# GroundStationvpatryk.net
KiCad netlist of a schematic drawn in EAGLE
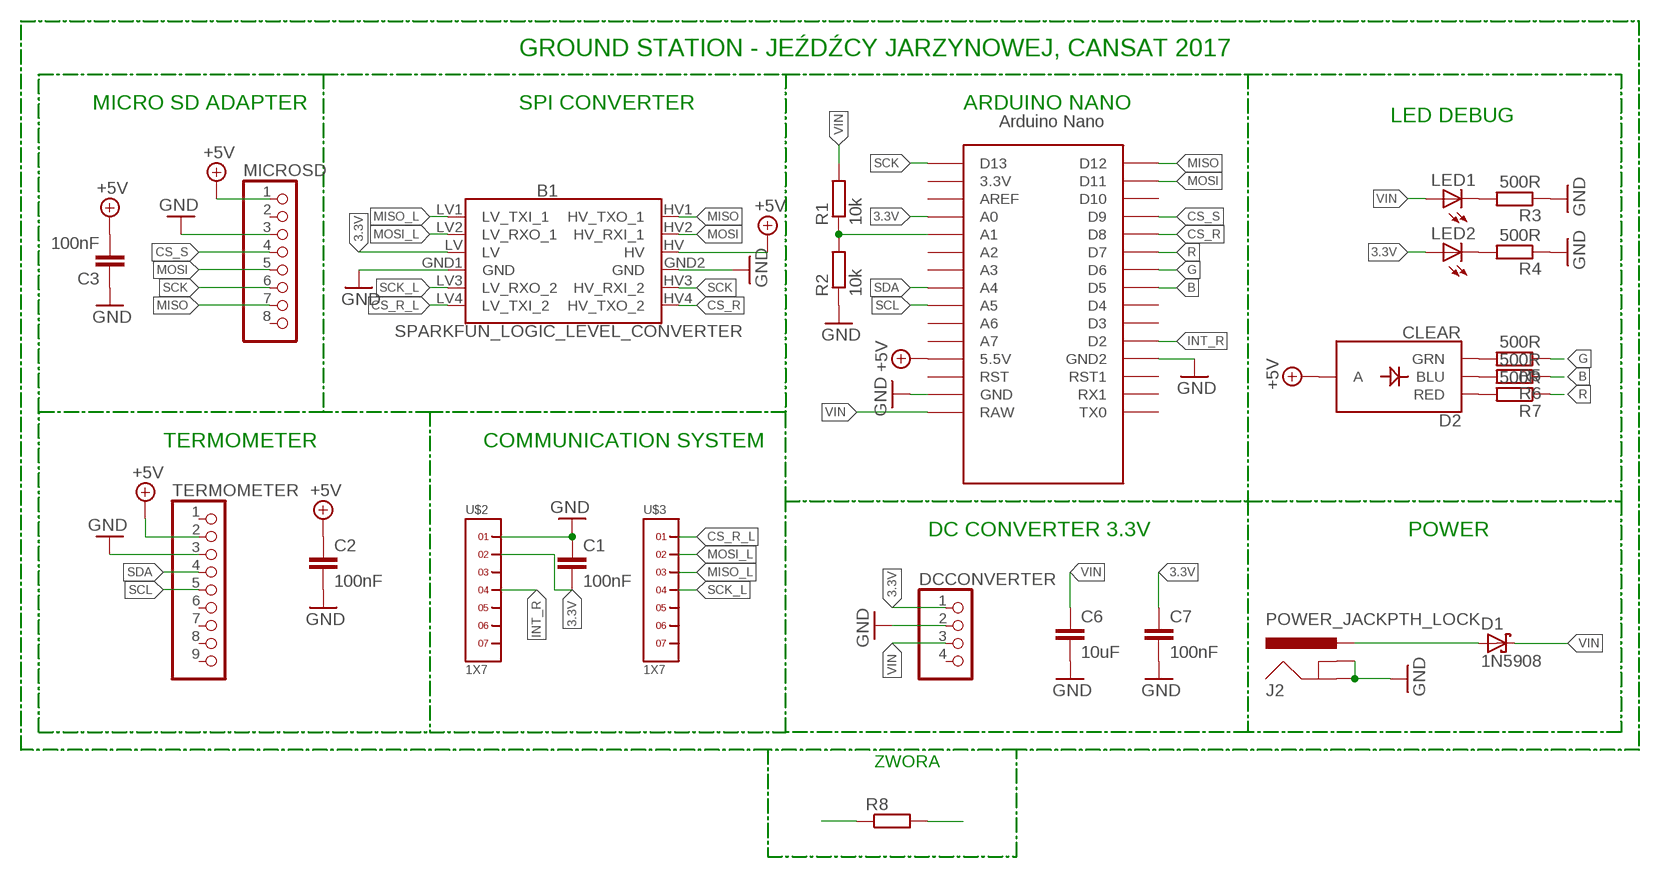
[diagram p0: schematic, sheet 1]

(export (version "E")
  (design (tool "Eeschema 10.0.6"))
  (components
    (comp (ref "B1")
      (value "SPARKFUN_LOGIC_LEVEL_CONVERTER")
      (footprint "eagle-import:SPARKFUN_LOGIC_LEVEL_CONVERTER")
      (libsource (lib "eagle-import") (part "SPARKFUN_LOGIC_LEVEL_CONVERTER"))
    )
    (comp (ref "C1")
      (value "100nF")
      (footprint "eagle-import:C050-025X075")
      (libsource (lib "eagle-import") (part "C-EU050-025X075"))
    )
    (comp (ref "C2")
      (value "100nF")
      (footprint "eagle-import:C050-025X075")
      (libsource (lib "eagle-import") (part "C-EU050-025X075"))
    )
    (comp (ref "C3")
      (value "100nF")
      (footprint "eagle-import:C050-025X075")
      (libsource (lib "eagle-import") (part "C-EU050-025X075"))
    )
    (comp (ref "C6")
      (value "10uF")
      (footprint "eagle-import:C050-025X075")
      (libsource (lib "eagle-import") (part "C-EU050-025X075"))
    )
    (comp (ref "C7")
      (value "100nF")
      (footprint "eagle-import:C050-025X075")
      (libsource (lib "eagle-import") (part "C-EU050-025X075"))
    )
    (comp (ref "D1")
      (value "1N5908")
      (footprint "eagle-import:C4111-15")
      (libsource (lib "eagle-import") (part "1N5908"))
    )
    (comp (ref "D2")
      (value "CLEAR")
      (footprint "eagle-import:LED-RGB-THRU")
      (libsource (lib "eagle-import") (part "LED-RGB-CACLEAR"))
    )
    (comp (ref "DCCONVERTER")
      (value "PINHD-1X4")
      (footprint "eagle-import:1X04")
      (libsource (lib "eagle-import") (part "PINHD-1X4"))
    )
    (comp (ref "J2")
      (value "POWER_JACKPTH_LOCK")
      (footprint "eagle-import:POWER_JACK_PTH_LOCK")
      (libsource (lib "eagle-import") (part "POWER_JACKPTH_LOCK"))
    )
    (comp (ref "LED1")
      (value "LED3MM")
      (footprint "eagle-import:LED3MM")
      (libsource (lib "eagle-import") (part "LED3MM"))
    )
    (comp (ref "LED2")
      (value "LED3MM")
      (footprint "eagle-import:LED3MM")
      (libsource (lib "eagle-import") (part "LED3MM"))
    )
    (comp (ref "MICROSD")
      (value "PINHD-1X8")
      (footprint "eagle-import:1X08")
      (libsource (lib "eagle-import") (part "PINHD-1X8"))
    )
    (comp (ref "R1")
      (value "10k")
      (footprint "eagle-import:0207_7")
      (libsource (lib "eagle-import") (part "R-EU_0207/7"))
    )
    (comp (ref "R2")
      (value "10k")
      (footprint "eagle-import:0207_7")
      (libsource (lib "eagle-import") (part "R-EU_0207/7"))
    )
    (comp (ref "R3")
      (value "500R")
      (footprint "eagle-import:0207_7")
      (libsource (lib "eagle-import") (part "R-EU_0207/7"))
    )
    (comp (ref "R4")
      (value "500R")
      (footprint "eagle-import:0207_7")
      (libsource (lib "eagle-import") (part "R-EU_0207/7"))
    )
    (comp (ref "R5")
      (value "500R")
      (footprint "eagle-import:0207_7")
      (libsource (lib "eagle-import") (part "R-EU_0207/7"))
    )
    (comp (ref "R6")
      (value "500R")
      (footprint "eagle-import:0207_7")
      (libsource (lib "eagle-import") (part "R-EU_0207/7"))
    )
    (comp (ref "R7")
      (value "500R")
      (footprint "eagle-import:0207_7")
      (libsource (lib "eagle-import") (part "R-EU_0207/7"))
    )
    (comp (ref "R8")
      (value "R-EU_0207/5V")
      (footprint "eagle-import:0207_5V")
      (libsource (lib "eagle-import") (part "R-EU_0207/5V"))
    )
    (comp (ref "TERMOMETER")
      (value "PINHD-1X9")
      (footprint "eagle-import:1X09")
      (libsource (lib "eagle-import") (part "PINHD-1X9"))
    )
    (comp (ref "U$1")
      (value "NANO")
      (footprint "eagle-import:NANO")
      (libsource (lib "eagle-import") (part "NANO"))
    )
    (comp (ref "U$2")
      (value "1X7")
      (footprint "eagle-import:1X7")
      (libsource (lib "eagle-import") (part "1X7"))
    )
    (comp (ref "U$3")
      (value "1X7")
      (footprint "eagle-import:1X7")
      (libsource (lib "eagle-import") (part "1X7"))
    )
  )
  (nets
    (net (code "1") (name "+5V") (class "Default")
      (node (ref "B1") (pin "HV") (pinfunction "HV_HV") (pintype "power_in"))
      (node (ref "C2") (pin "1") (pinfunction "1_1") (pintype "passive"))
      (node (ref "C3") (pin "2") (pinfunction "2_2") (pintype "passive"))
      (node (ref "D2") (pin "2") (pinfunction "A_2") (pintype "bidirectional"))
      (node (ref "MICROSD") (pin "1") (pinfunction "1_1") (pintype "passive"))
      (node (ref "TERMOMETER") (pin "2") (pinfunction "2_2") (pintype "passive"))
      (node (ref "U$1") (pin "5V") (pinfunction "5.5V_5V") (pintype "bidirectional"))
    )
    (net (code "2") (name "3.3V") (class "Default")
      (node (ref "B1") (pin "LV") (pinfunction "LV_LV") (pintype "power_in"))
      (node (ref "C1") (pin "2") (pinfunction "2_2") (pintype "passive"))
      (node (ref "C7") (pin "1") (pinfunction "1_1") (pintype "passive"))
      (node (ref "DCCONVERTER") (pin "1") (pinfunction "1_1") (pintype "passive"))
      (node (ref "LED2") (pin "A") (pinfunction "A_A") (pintype "passive"))
      (node (ref "U$1") (pin "A0") (pinfunction "A0_A0") (pintype "bidirectional"))
      (node (ref "U$2") (pin "2") (pinfunction "2_2") (pintype "bidirectional"))
    )
    (net (code "3") (name "B") (class "Default")
      (node (ref "R6") (pin "1") (pinfunction "1_1") (pintype "passive"))
      (node (ref "U$1") (pin "D5") (pinfunction "D5_D5") (pintype "bidirectional"))
    )
    (net (code "4") (name "CS_R") (class "Default")
      (node (ref "B1") (pin "HV4") (pinfunction "HV_TXO_2_HV4") (pintype "bidirectional"))
      (node (ref "U$1") (pin "D8") (pinfunction "D8_D8") (pintype "bidirectional"))
    )
    (net (code "5") (name "CS_R_L") (class "Default")
      (node (ref "B1") (pin "LV4") (pinfunction "LV_TXI_2_LV4") (pintype "bidirectional"))
      (node (ref "U$3") (pin "1") (pinfunction "1_1") (pintype "bidirectional"))
    )
    (net (code "6") (name "CS_S") (class "Default")
      (node (ref "MICROSD") (pin "4") (pinfunction "4_4") (pintype "passive"))
      (node (ref "U$1") (pin "D9") (pinfunction "D9_D9") (pintype "bidirectional"))
    )
    (net (code "7") (name "G") (class "Default")
      (node (ref "R5") (pin "1") (pinfunction "1_1") (pintype "passive"))
      (node (ref "U$1") (pin "D6") (pinfunction "D6_D6") (pintype "bidirectional"))
    )
    (net (code "8") (name "GND") (class "Default")
      (node (ref "B1") (pin "GND1") (pinfunction "GND_GND1") (pintype "power_in"))
      (node (ref "B1") (pin "GND2") (pinfunction "GND_GND2") (pintype "power_in"))
      (node (ref "C1") (pin "1") (pinfunction "1_1") (pintype "passive"))
      (node (ref "C2") (pin "2") (pinfunction "2_2") (pintype "passive"))
      (node (ref "C3") (pin "1") (pinfunction "1_1") (pintype "passive"))
      (node (ref "C6") (pin "2") (pinfunction "2_2") (pintype "passive"))
      (node (ref "C7") (pin "2") (pinfunction "2_2") (pintype "passive"))
      (node (ref "DCCONVERTER") (pin "2") (pinfunction "2_2") (pintype "passive"))
      (node (ref "J2") (pin "GND") (pinfunction "GND_GND") (pintype "bidirectional"))
      (node (ref "J2") (pin "GNDBREAK") (pinfunction "GNDBREAK_GNDBREAK") (pintype "bidirectional"))
      (node (ref "MICROSD") (pin "3") (pinfunction "3_3") (pintype "passive"))
      (node (ref "R2") (pin "1") (pinfunction "1_1") (pintype "passive"))
      (node (ref "R3") (pin "1") (pinfunction "1_1") (pintype "passive"))
      (node (ref "R4") (pin "1") (pinfunction "1_1") (pintype "passive"))
      (node (ref "TERMOMETER") (pin "3") (pinfunction "3_3") (pintype "passive"))
      (node (ref "U$1") (pin "GND") (pinfunction "GND_GND") (pintype "bidirectional"))
      (node (ref "U$1") (pin "GND1") (pinfunction "GND2_GND1") (pintype "bidirectional"))
      (node (ref "U$2") (pin "1") (pinfunction "1_1") (pintype "bidirectional"))
    )
    (net (code "9") (name "INT_R") (class "Default")
      (node (ref "U$1") (pin "D2") (pinfunction "D2_D2") (pintype "bidirectional"))
      (node (ref "U$2") (pin "4") (pinfunction "4_4") (pintype "bidirectional"))
    )
    (net (code "10") (name "MISO") (class "Default")
      (node (ref "B1") (pin "HV1") (pinfunction "HV_TXO_1_HV1") (pintype "bidirectional"))
      (node (ref "MICROSD") (pin "7") (pinfunction "7_7") (pintype "passive"))
      (node (ref "R8") (pin "1") (pinfunction "1_1") (pintype "passive"))
      (node (ref "R8") (pin "2") (pinfunction "2_2") (pintype "passive"))
      (node (ref "U$1") (pin "D12") (pinfunction "D12_D12") (pintype "bidirectional"))
    )
    (net (code "11") (name "MISO_L") (class "Default")
      (node (ref "B1") (pin "LV1") (pinfunction "LV_TXI_1_LV1") (pintype "bidirectional"))
      (node (ref "U$3") (pin "3") (pinfunction "3_3") (pintype "bidirectional"))
    )
    (net (code "12") (name "MOSI") (class "Default")
      (node (ref "B1") (pin "HV2") (pinfunction "HV_RXI_1_HV2") (pintype "bidirectional"))
      (node (ref "MICROSD") (pin "5") (pinfunction "5_5") (pintype "passive"))
      (node (ref "U$1") (pin "D11") (pinfunction "D11_D11") (pintype "bidirectional"))
    )
    (net (code "13") (name "MOSI_L") (class "Default")
      (node (ref "B1") (pin "LV2") (pinfunction "LV_RXO_1_LV2") (pintype "bidirectional"))
      (node (ref "U$3") (pin "2") (pinfunction "2_2") (pintype "bidirectional"))
    )
    (net (code "14") (name "Net-(D1-PadA)") (class "Default")
      (node (ref "D1") (pin "A") (pinfunction "A_A") (pintype "passive"))
      (node (ref "J2") (pin "PWR") (pinfunction "PWR_PWR") (pintype "bidirectional"))
    )
    (net (code "15") (name "Net-(D2-BLU)") (class "Default")
      (node (ref "D2") (pin "4") (pinfunction "BLU_4") (pintype "bidirectional"))
      (node (ref "R6") (pin "2") (pinfunction "2_2") (pintype "passive"))
    )
    (net (code "16") (name "Net-(D2-GRN)") (class "Default")
      (node (ref "D2") (pin "3") (pinfunction "GRN_3") (pintype "bidirectional"))
      (node (ref "R5") (pin "2") (pinfunction "2_2") (pintype "passive"))
    )
    (net (code "17") (name "Net-(D2-RED)") (class "Default")
      (node (ref "D2") (pin "1") (pinfunction "RED_1") (pintype "bidirectional"))
      (node (ref "R7") (pin "2") (pinfunction "2_2") (pintype "passive"))
    )
    (net (code "18") (name "Net-(LED1-C)") (class "Default")
      (node (ref "LED1") (pin "K") (pinfunction "C_K") (pintype "passive"))
      (node (ref "R3") (pin "2") (pinfunction "2_2") (pintype "passive"))
    )
    (net (code "19") (name "Net-(LED2-C)") (class "Default")
      (node (ref "LED2") (pin "K") (pinfunction "C_K") (pintype "passive"))
      (node (ref "R4") (pin "2") (pinfunction "2_2") (pintype "passive"))
    )
    (net (code "20") (name "Net-(R1-Pad1)") (class "Default")
      (node (ref "R1") (pin "1") (pinfunction "1_1") (pintype "passive"))
      (node (ref "R2") (pin "2") (pinfunction "2_2") (pintype "passive"))
      (node (ref "U$1") (pin "A1") (pinfunction "A1_A1") (pintype "bidirectional"))
    )
    (net (code "21") (name "R") (class "Default")
      (node (ref "R7") (pin "1") (pinfunction "1_1") (pintype "passive"))
      (node (ref "U$1") (pin "D7") (pinfunction "D7_D7") (pintype "bidirectional"))
    )
    (net (code "22") (name "SCK") (class "Default")
      (node (ref "B1") (pin "HV3") (pinfunction "HV_RXI_2_HV3") (pintype "bidirectional"))
      (node (ref "MICROSD") (pin "6") (pinfunction "6_6") (pintype "passive"))
      (node (ref "U$1") (pin "D13") (pinfunction "D13_D13") (pintype "bidirectional"))
    )
    (net (code "23") (name "SCK_L") (class "Default")
      (node (ref "B1") (pin "LV3") (pinfunction "LV_RXO_2_LV3") (pintype "bidirectional"))
      (node (ref "U$3") (pin "4") (pinfunction "4_4") (pintype "bidirectional"))
    )
    (net (code "24") (name "SCL") (class "Default")
      (node (ref "TERMOMETER") (pin "5") (pinfunction "5_5") (pintype "passive"))
      (node (ref "U$1") (pin "A5") (pinfunction "A5_A5") (pintype "bidirectional"))
    )
    (net (code "25") (name "SDA") (class "Default")
      (node (ref "TERMOMETER") (pin "4") (pinfunction "4_4") (pintype "passive"))
      (node (ref "U$1") (pin "A4") (pinfunction "A4_A4") (pintype "bidirectional"))
    )
    (net (code "26") (name "VIN") (class "Default")
      (node (ref "C6") (pin "1") (pinfunction "1_1") (pintype "passive"))
      (node (ref "D1") (pin "C") (pinfunction "C_C") (pintype "passive"))
      (node (ref "DCCONVERTER") (pin "3") (pinfunction "3_3") (pintype "passive"))
      (node (ref "LED1") (pin "A") (pinfunction "A_A") (pintype "passive"))
      (node (ref "R1") (pin "2") (pinfunction "2_2") (pintype "passive"))
      (node (ref "U$1") (pin "RAW") (pinfunction "RAW_RAW") (pintype "bidirectional"))
    )
    (net (code "27") (name "unconnected-(DCCONVERTER-Pad4)") (class "Default")
      (node (ref "DCCONVERTER") (pin "4") (pinfunction "4_4") (pintype "passive"))
    )
    (net (code "28") (name "unconnected-(MICROSD-Pad2)") (class "Default")
      (node (ref "MICROSD") (pin "2") (pinfunction "2_2") (pintype "passive"))
    )
    (net (code "29") (name "unconnected-(MICROSD-Pad8)") (class "Default")
      (node (ref "MICROSD") (pin "8") (pinfunction "8_8") (pintype "passive"))
    )
    (net (code "30") (name "unconnected-(TERMOMETER-Pad1)") (class "Default")
      (node (ref "TERMOMETER") (pin "1") (pinfunction "1_1") (pintype "passive"))
    )
    (net (code "31") (name "unconnected-(TERMOMETER-Pad6)") (class "Default")
      (node (ref "TERMOMETER") (pin "6") (pinfunction "6_6") (pintype "passive"))
    )
    (net (code "32") (name "unconnected-(TERMOMETER-Pad7)") (class "Default")
      (node (ref "TERMOMETER") (pin "7") (pinfunction "7_7") (pintype "passive"))
    )
    (net (code "33") (name "unconnected-(TERMOMETER-Pad8)") (class "Default")
      (node (ref "TERMOMETER") (pin "8") (pinfunction "8_8") (pintype "passive"))
    )
    (net (code "34") (name "unconnected-(TERMOMETER-Pad9)") (class "Default")
      (node (ref "TERMOMETER") (pin "9") (pinfunction "9_9") (pintype "passive"))
    )
    (net (code "35") (name "unconnected-(U$1-Pad3.3V)") (class "Default")
      (node (ref "U$1") (pin "3.3V") (pinfunction "3.3V_3.3V") (pintype "bidirectional"))
    )
    (net (code "36") (name "unconnected-(U$1-PadA2)") (class "Default")
      (node (ref "U$1") (pin "A2") (pinfunction "A2_A2") (pintype "bidirectional"))
    )
    (net (code "37") (name "unconnected-(U$1-PadA3)") (class "Default")
      (node (ref "U$1") (pin "A3") (pinfunction "A3_A3") (pintype "bidirectional"))
    )
    (net (code "38") (name "unconnected-(U$1-PadA6)") (class "Default")
      (node (ref "U$1") (pin "A6") (pinfunction "A6_A6") (pintype "bidirectional"))
    )
    (net (code "39") (name "unconnected-(U$1-PadA7)") (class "Default")
      (node (ref "U$1") (pin "A7") (pinfunction "A7_A7") (pintype "bidirectional"))
    )
    (net (code "40") (name "unconnected-(U$1-PadAREF)") (class "Default")
      (node (ref "U$1") (pin "AREF") (pinfunction "AREF_AREF") (pintype "bidirectional"))
    )
    (net (code "41") (name "unconnected-(U$1-PadD3)") (class "Default")
      (node (ref "U$1") (pin "D3") (pinfunction "D3_D3") (pintype "bidirectional"))
    )
    (net (code "42") (name "unconnected-(U$1-PadD4)") (class "Default")
      (node (ref "U$1") (pin "D4") (pinfunction "D4_D4") (pintype "bidirectional"))
    )
    (net (code "43") (name "unconnected-(U$1-PadD10)") (class "Default")
      (node (ref "U$1") (pin "D10") (pinfunction "D10_D10") (pintype "bidirectional"))
    )
    (net (code "44") (name "unconnected-(U$1-PadICSP1)") (class "Default")
      (node (ref "U$1") (pin "ICSP1") (pinfunction "ICSP1_ICSP1") (pintype "bidirectional"))
    )
    (net (code "45") (name "unconnected-(U$1-PadICSP2)") (class "Default")
      (node (ref "U$1") (pin "ICSP2") (pinfunction "ICSP2_ICSP2") (pintype "bidirectional"))
    )
    (net (code "46") (name "unconnected-(U$1-PadICSP3)") (class "Default")
      (node (ref "U$1") (pin "ICSP3") (pinfunction "ICSP3_ICSP3") (pintype "bidirectional"))
    )
    (net (code "47") (name "unconnected-(U$1-PadICSP4)") (class "Default")
      (node (ref "U$1") (pin "ICSP4") (pinfunction "ICSP4_ICSP4") (pintype "bidirectional"))
    )
    (net (code "48") (name "unconnected-(U$1-PadICSP5)") (class "Default")
      (node (ref "U$1") (pin "ICSP5") (pinfunction "ICSP5_ICSP5") (pintype "bidirectional"))
    )
    (net (code "49") (name "unconnected-(U$1-PadICSP6)") (class "Default")
      (node (ref "U$1") (pin "ICSP6") (pinfunction "ICSP6_ICSP6") (pintype "bidirectional"))
    )
    (net (code "50") (name "unconnected-(U$1-PadRST)") (class "Default")
      (node (ref "U$1") (pin "RST") (pinfunction "RST_RST") (pintype "bidirectional"))
    )
    (net (code "51") (name "unconnected-(U$1-PadRST1)") (class "Default")
      (node (ref "U$1") (pin "RST1") (pinfunction "RST1_RST1") (pintype "bidirectional"))
    )
    (net (code "52") (name "unconnected-(U$1-PadRX1)") (class "Default")
      (node (ref "U$1") (pin "RX1") (pinfunction "RX1_RX1") (pintype "bidirectional"))
    )
    (net (code "53") (name "unconnected-(U$1-PadTX0)") (class "Default")
      (node (ref "U$1") (pin "TX0") (pinfunction "TX0_TX0") (pintype "bidirectional"))
    )
    (net (code "54") (name "unconnected-(U$2-Pad3)") (class "Default")
      (node (ref "U$2") (pin "3") (pinfunction "3_3") (pintype "bidirectional"))
    )
    (net (code "55") (name "unconnected-(U$2-Pad5)") (class "Default")
      (node (ref "U$2") (pin "5") (pinfunction "5_5") (pintype "bidirectional"))
    )
    (net (code "56") (name "unconnected-(U$2-Pad6)") (class "Default")
      (node (ref "U$2") (pin "6") (pinfunction "6_6") (pintype "bidirectional"))
    )
    (net (code "57") (name "unconnected-(U$2-Pad7)") (class "Default")
      (node (ref "U$2") (pin "7") (pinfunction "7_7") (pintype "bidirectional"))
    )
    (net (code "58") (name "unconnected-(U$3-Pad5)") (class "Default")
      (node (ref "U$3") (pin "5") (pinfunction "5_5") (pintype "bidirectional"))
    )
    (net (code "59") (name "unconnected-(U$3-Pad6)") (class "Default")
      (node (ref "U$3") (pin "6") (pinfunction "6_6") (pintype "bidirectional"))
    )
    (net (code "60") (name "unconnected-(U$3-Pad7)") (class "Default")
      (node (ref "U$3") (pin "7") (pinfunction "7_7") (pintype "bidirectional"))
    )
  )
)
